# HV_Module_2W.net
KiCad netlist of a schematic drawn in Altium Designer
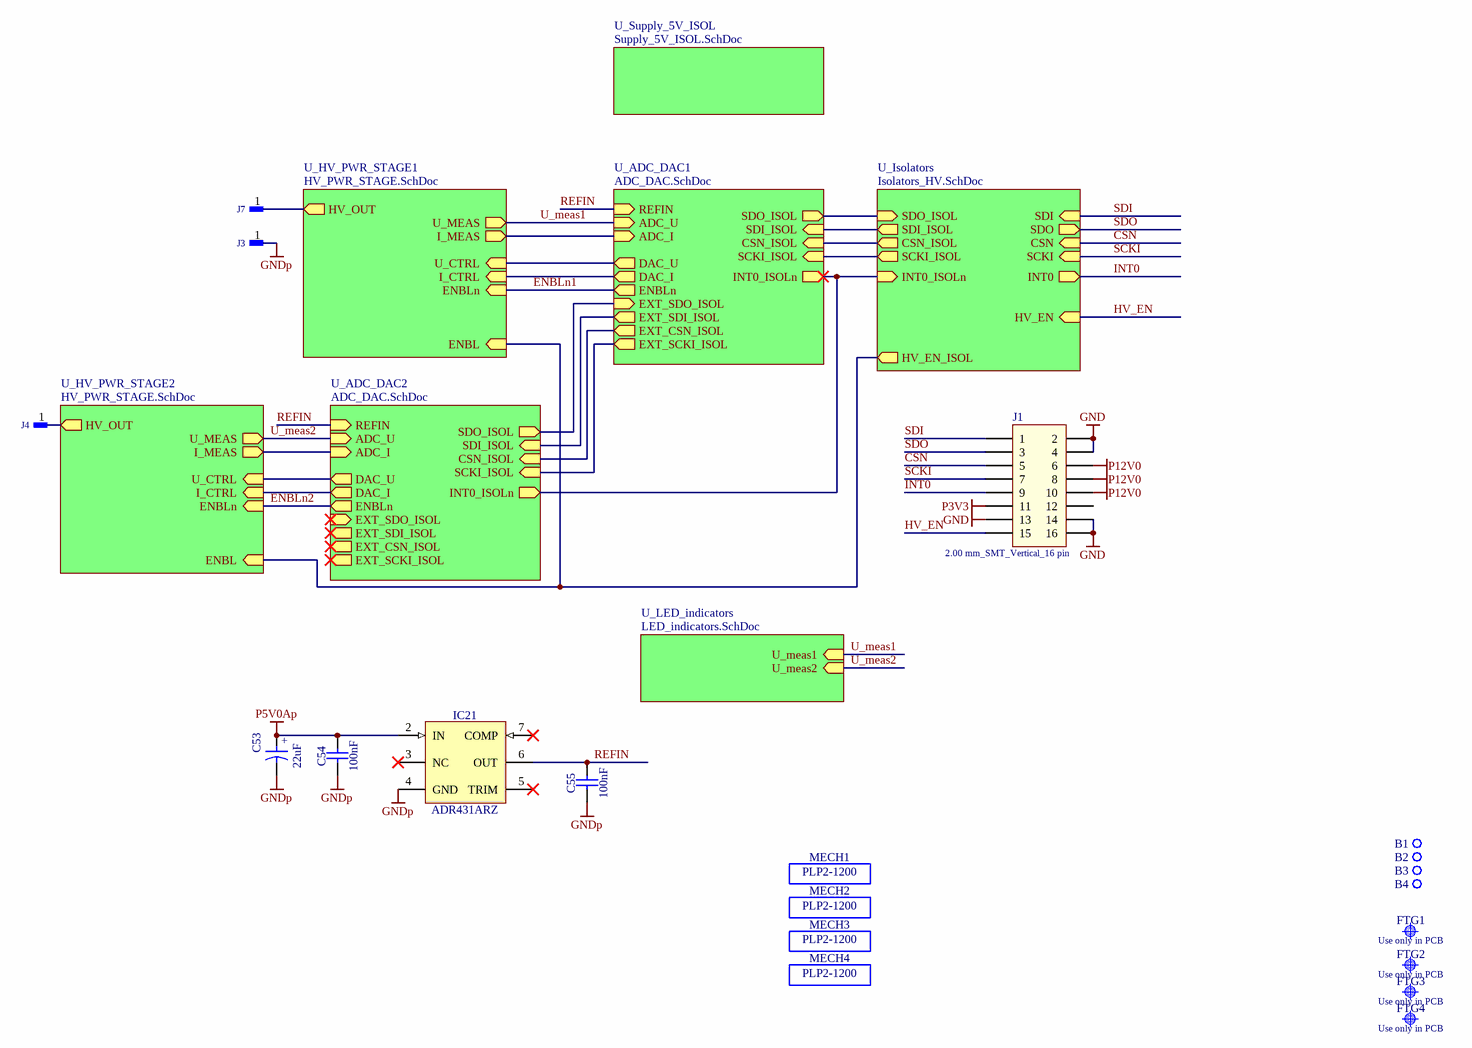
[diagram p0: HV_Module_2W.schdoc]

(export (version "E")
  (design (tool "Eeschema 10.0.6"))
  (components
    (comp (ref "B1")
      (value "Plated Hole")
      (footprint "MTG270_500")
      (description "Single Terminal Socket")
      (fields (field (name "PART NUMBER") "PLATED_HOLE2.7_PAD5.0") (field (name "AUTHOR") "CERN DEM JMW"))
      (libsource (lib "Eletro-mechanical") (part "Single Terminal Socket"))
    )
    (comp (ref "B2")
      (value "Plated Hole")
      (footprint "MTG270_500")
      (description "Single Terminal Socket")
      (fields (field (name "PART NUMBER") "PLATED_HOLE2.7_PAD5.0") (field (name "AUTHOR") "CERN DEM JMW"))
      (libsource (lib "Eletro-mechanical") (part "Single Terminal Socket"))
    )
    (comp (ref "B3")
      (value "Plated Hole")
      (footprint "MTG270_500")
      (description "Single Terminal Socket")
      (fields (field (name "PART NUMBER") "PLATED_HOLE2.7_PAD5.0") (field (name "AUTHOR") "CERN DEM JMW"))
      (libsource (lib "Eletro-mechanical") (part "Single Terminal Socket"))
    )
    (comp (ref "B4")
      (value "Plated Hole")
      (footprint "MTG270_500")
      (description "Single Terminal Socket")
      (fields (field (name "PART NUMBER") "PLATED_HOLE2.7_PAD5.0") (field (name "AUTHOR") "CERN DEM JMW"))
      (libsource (lib "Eletro-mechanical") (part "Single Terminal Socket"))
    )
    (comp (ref "C53")
      (value "22uF")
      (footprint "CAPMP3528X210N")
      (description "Polarised capacitor")
      (fields
        (field (name "PART NUMBER") "CTE3528-21_22UF_20V_10%")
        (field (name "VOLTAGE") "20V")
        (field (name "AUTHOR") "CERN DEM JLC")
      )
      (libsource (lib "Capacitors") (part "Capacitor - polarized"))
    )
    (comp (ref "C54")
      (value "100nF")
      (footprint "CAPC1005X55N")
      (description "Non-polarised capacitor")
      (fields
        (field (name "PART NUMBER") "CC0402_100NF_16V_10%_X7R")
        (field (name "VOLTAGE") "16V")
        (field (name "AUTHOR") "CERN DEM JLC")
      )
      (libsource (lib "Capacitors") (part "Capacitor - non polarized"))
    )
    (comp (ref "C55")
      (value "100nF")
      (footprint "CAPC1005X55N")
      (description "Non-polarised capacitor")
      (fields
        (field (name "PART NUMBER") "CC0402_100NF_16V_10%_X7R")
        (field (name "VOLTAGE") "16V")
        (field (name "AUTHOR") "CERN DEM JLC")
      )
      (libsource (lib "Capacitors") (part "Capacitor - non polarized"))
    )
    (comp (ref "FTG1")
      (value "Use only in PCB")
      (footprint "FIDUCIAL_TOP_C100-200")
      (description "Fiducial Target")
      (fields (field (name "PART NUMBER") "FIDUCIAL_TARGET_C100-200") (field (name "AUTHOR") "CERN DEM JLC"))
      (libsource (lib "Eletro-mechanical") (part "Fiducial Target"))
    )
    (comp (ref "FTG2")
      (value "Use only in PCB")
      (footprint "FIDUCIAL_TOP_S100-200")
      (description "Fiducial Target")
      (fields (field (name "PART NUMBER") "FIDUCIAL_TARGET_S100-200") (field (name "AUTHOR") "CERN DEM JLC"))
      (libsource (lib "Eletro-mechanical") (part "Fiducial Target"))
    )
    (comp (ref "FTG3")
      (value "Use only in PCB")
      (footprint "FIDUCIAL_TOP_S100-200")
      (description "Fiducial Target")
      (fields (field (name "PART NUMBER") "FIDUCIAL_TARGET_S100-200") (field (name "AUTHOR") "CERN DEM JLC"))
      (libsource (lib "Eletro-mechanical") (part "Fiducial Target"))
    )
    (comp (ref "FTG4")
      (value "Use only in PCB")
      (footprint "FIDUCIAL_TOP_S100-200")
      (description "Fiducial Target")
      (fields (field (name "PART NUMBER") "FIDUCIAL_TARGET_S100-200") (field (name "AUTHOR") "CERN DEM JLC"))
      (libsource (lib "Eletro-mechanical") (part "Fiducial Target"))
    )
    (comp (ref "IC21")
      (value "ADR431ARZ")
      (footprint "SOIC127P600X175-8N")
      (fields (field (name "MANUFACTURER") "ANALOG DEVICES") (field (name "AUTHOR") "CERN DEM JLC"))
      (libsource (lib "ICs And Semiconductors") (part "ADR431"))
    )
    (comp (ref "J1")
      (value "2.00 mm_SMT_Vertical_16 pin")
      (footprint "62131621821")
      (description "Socket Header WR-PHD, Pitch 2.00 mm, SMT, Vertical, dual row, 16 pin")
      (fields (field (name "PART NUMBER") "62131621821") (field (name "PUBLISHER") "Wurth Elektronik"))
      (libsource (lib "ALTIUM-PHD_2_0_SMT_DUAL_SOCKET_HEADER_LOW_PROFILE_REEL_6213XX21821-rev18a") (part "62131621821"))
    )
    (comp (ref "J3")
      (value "SMD Pad")
      (footprint "R400X300")
      (description "Single SMD Pad")
      (fields (field (name "PART NUMBER") "SMD_PAD_4X3MM") (field (name "AUTHOR") "CERN DEM JLC"))
      (libsource (lib "Eletro-mechanical") (part "Single SMD Pad"))
    )
    (comp (ref "J4")
      (value "SMD Pad")
      (footprint "R400X300")
      (description "Single SMD Pad")
      (fields (field (name "PART NUMBER") "SMD_PAD_4X3MM") (field (name "AUTHOR") "CERN DEM JLC"))
      (libsource (lib "Eletro-mechanical") (part "Single SMD Pad"))
    )
    (comp (ref "J7")
      (value "SMD Pad")
      (footprint "R400X300")
      (description "Single SMD Pad")
      (fields (field (name "PART NUMBER") "SMD_PAD_4X3MM") (field (name "AUTHOR") "CERN DEM JLC"))
      (libsource (lib "Eletro-mechanical") (part "Single SMD Pad"))
    )
    (comp (ref "MECH1")
      (value "PLP2-1200")
      (footprint "GENERIC_MECH")
      (description "Lightguide")
      (fields (field (name "MANUFACTURER") "BIvar") (field (name "AUTHOR") "GK"))
      (libsource (lib "Mechanical") (part "Generic_mechanical"))
    )
    (comp (ref "MECH2")
      (value "PLP2-1200")
      (footprint "GENERIC_MECH")
      (description "Lightguide")
      (fields (field (name "MANUFACTURER") "BIvar") (field (name "AUTHOR") "GK"))
      (libsource (lib "Mechanical") (part "Generic_mechanical"))
    )
    (comp (ref "MECH3")
      (value "PLP2-1200")
      (footprint "GENERIC_MECH")
      (description "Lightguide")
      (fields (field (name "MANUFACTURER") "BIvar") (field (name "AUTHOR") "GK"))
      (libsource (lib "Mechanical") (part "Generic_mechanical"))
    )
    (comp (ref "MECH4")
      (value "PLP2-1200")
      (footprint "GENERIC_MECH")
      (description "Lightguide")
      (fields (field (name "MANUFACTURER") "BIvar") (field (name "AUTHOR") "GK"))
      (libsource (lib "Mechanical") (part "Generic_mechanical"))
    )
  )
  (nets
    (net (code "1") (name "/CSN") (class "Default")
      (node (ref "J1") (pin "5") (pinfunction "5_5") (pintype "passive"))
    )
    (net (code "16") (name "/HV_EN") (class "Default")
      (node (ref "J1") (pin "15") (pinfunction "15_15") (pintype "passive"))
    )
    (net (code "18") (name "/HV_OUT") (class "Default")
      (node (ref "J7") (pin "1") (pinfunction "1_1") (pintype "bidirectional"))
    )
    (net (code "19") (name "/HV_OUT_1") (class "Default")
      (node (ref "J4") (pin "1") (pinfunction "1_1") (pintype "bidirectional"))
    )
    (net (code "20") (name "/INT0") (class "Default")
      (node (ref "J1") (pin "9") (pinfunction "9_9") (pintype "passive"))
    )
    (net (code "24") (name "/REFIN") (class "Default")
      (node (ref "C55") (pin "2") (pinfunction "2_2") (pintype "passive"))
      (node (ref "IC21") (pin "6") (pinfunction "OUT_6") (pintype "power_in"))
    )
    (net (code "25") (name "/SCKI") (class "Default")
      (node (ref "J1") (pin "7") (pinfunction "7_7") (pintype "passive"))
    )
    (net (code "27") (name "/SDI") (class "Default")
      (node (ref "J1") (pin "1") (pinfunction "1_1") (pintype "passive"))
    )
    (net (code "29") (name "/SDO") (class "Default")
      (node (ref "J1") (pin "3") (pinfunction "3_3") (pintype "passive"))
    )
    (net (code "34") (name "GND") (class "Default")
      (node (ref "J1") (pin "13") (pinfunction "13_13") (pintype "passive"))
      (node (ref "J1") (pin "14") (pinfunction "14_14") (pintype "passive"))
      (node (ref "J1") (pin "16") (pinfunction "16_16") (pintype "passive"))
      (node (ref "J1") (pin "2") (pinfunction "2_2") (pintype "passive"))
      (node (ref "J1") (pin "4") (pinfunction "4_4") (pintype "passive"))
    )
    (net (code "35") (name "GNDp") (class "Default")
      (node (ref "C53") (pin "2") (pinfunction "2_2") (pintype "passive"))
      (node (ref "C54") (pin "1") (pinfunction "1_1") (pintype "passive"))
      (node (ref "C55") (pin "1") (pinfunction "1_1") (pintype "passive"))
      (node (ref "IC21") (pin "4") (pinfunction "GND_4") (pintype "power_in"))
      (node (ref "J3") (pin "1") (pinfunction "1_1") (pintype "bidirectional"))
    )
    (net (code "36") (name "P3V3") (class "Default")
      (node (ref "J1") (pin "11") (pinfunction "11_11") (pintype "passive"))
    )
    (net (code "37") (name "P5V0Ap") (class "Default")
      (node (ref "C53") (pin "1") (pinfunction "1_1") (pintype "passive"))
      (node (ref "C54") (pin "2") (pinfunction "2_2") (pintype "passive"))
      (node (ref "IC21") (pin "2") (pinfunction "IN_2") (pintype "input"))
    )
    (net (code "38") (name "P12V0") (class "Default")
      (node (ref "J1") (pin "10") (pinfunction "10_10") (pintype "passive"))
      (node (ref "J1") (pin "6") (pinfunction "6_6") (pintype "passive"))
      (node (ref "J1") (pin "8") (pinfunction "8_8") (pintype "passive"))
    )
    (net (code "39") (name "unconnected-(B1-Pad1)") (class "Default")
      (node (ref "B1") (pin "1") (pinfunction "1_1") (pintype "bidirectional"))
    )
    (net (code "40") (name "unconnected-(B2-Pad1)") (class "Default")
      (node (ref "B2") (pin "1") (pinfunction "1_1") (pintype "bidirectional"))
    )
    (net (code "41") (name "unconnected-(B3-Pad1)") (class "Default")
      (node (ref "B3") (pin "1") (pinfunction "1_1") (pintype "bidirectional"))
    )
    (net (code "42") (name "unconnected-(B4-Pad1)") (class "Default")
      (node (ref "B4") (pin "1") (pinfunction "1_1") (pintype "bidirectional"))
    )
    (net (code "43") (name "unconnected-(IC21-COMP-Pad7)") (class "Default")
      (node (ref "IC21") (pin "7") (pinfunction "COMP_7") (pintype "input+no_connect"))
    )
    (net (code "44") (name "unconnected-(IC21-NC-Pad3)") (class "Default")
      (node (ref "IC21") (pin "3") (pinfunction "NC_3") (pintype "passive+no_connect"))
    )
    (net (code "45") (name "unconnected-(IC21-TRIM-Pad5)") (class "Default")
      (node (ref "IC21") (pin "5") (pinfunction "TRIM_5") (pintype "passive+no_connect"))
    )
    (net (code "46") (name "unconnected-(J1-Pad12)") (class "Default")
      (node (ref "J1") (pin "12") (pinfunction "12_12") (pintype "passive"))
    )
  )
)
